# Sheet2.net
KiCad netlist of a schematic drawn in Altium Designer
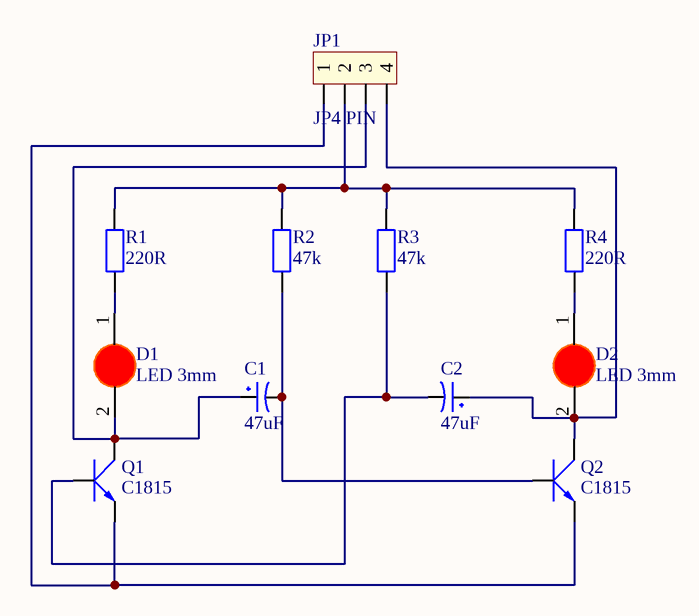
[diagram p0: Sheet2.SchDoc]

(export (version "E")
  (design (tool "Eeschema 10.0.6"))
  (components
    (comp (ref "C1")
      (value "47uF")
      (footprint "tu hoa 5mm")
      (description "Cắm")
      (libsource (lib "Capacitor") (part "Tu Hoa 47uF 16V 5x10"))
    )
    (comp (ref "C2")
      (value "47uF")
      (footprint "tu hoa 5mm")
      (description "Cắm")
      (libsource (lib "Capacitor") (part "Tu Hoa 47uF 16V 5x10"))
    )
    (comp (ref "D1")
      (value "LED 3mm")
      (footprint "LED-3MM-RED")
      (description "Cắm")
      (libsource (lib "Led") (part "LED 3mm Do"))
    )
    (comp (ref "D2")
      (value "LED 3mm")
      (footprint "LED-3MM-RED")
      (description "Cắm")
      (libsource (lib "Led") (part "LED 3mm Do"))
    )
    (comp (ref "JP1") (value "JP4 PIN") (footprint "JP4") (libsource (lib "Cty1") (part "JP4")))
    (comp (ref "Q1")
      (value "C1815")
      (footprint "TO92")
      (description "NPN transistor")
      (libsource (lib "TranFet") (part "Trans C1815 DIP"))
    )
    (comp (ref "Q2")
      (value "C1815")
      (footprint "TO92")
      (description "NPN transistor")
      (libsource (lib "TranFet") (part "Trans C1815 DIP"))
    )
    (comp (ref "R1")
      (value "220R")
      (footprint "tro vach 1/4w")
      (description "Cắm")
      (libsource (lib "Resistor") (part "Tro Vach 1/4W 5% 220R"))
    )
    (comp (ref "R2")
      (value "47k")
      (footprint "tro vach 1/4w")
      (description "Cắm")
      (libsource (lib "Resistor") (part "Tro Vach 1/4W 5% 47k"))
    )
    (comp (ref "R3")
      (value "47k")
      (footprint "tro vach 1/4w")
      (description "Cắm")
      (libsource (lib "Resistor") (part "Tro Vach 1/4W 5% 47k"))
    )
    (comp (ref "R4")
      (value "220R")
      (footprint "tro vach 1/4w")
      (description "Cắm")
      (libsource (lib "Resistor") (part "Tro Vach 1/4W 5% 220R"))
    )
  )
  (nets
    (net (code "1") (name "Net-(D1-A)") (class "Default")
      (node (ref "D1") (pin "1") (pinfunction "A_1") (pintype "passive"))
      (node (ref "R1") (pin "1") (pinfunction "1_1") (pintype "passive"))
    )
    (net (code "2") (name "Net-(D1-K)") (class "Default")
      (node (ref "C1") (pin "1") (pinfunction "1_1") (pintype "passive"))
      (node (ref "D1") (pin "2") (pinfunction "K_2") (pintype "passive"))
      (node (ref "JP1") (pin "3") (pinfunction "3_3") (pintype "passive"))
      (node (ref "Q1") (pin "2") (pinfunction "C_2") (pintype "passive"))
    )
    (net (code "3") (name "Net-(D2-A)") (class "Default")
      (node (ref "D2") (pin "1") (pinfunction "A_1") (pintype "passive"))
      (node (ref "R4") (pin "1") (pinfunction "1_1") (pintype "passive"))
    )
    (net (code "4") (name "Net-(D2-K)") (class "Default")
      (node (ref "C2") (pin "1") (pinfunction "1_1") (pintype "passive"))
      (node (ref "D2") (pin "2") (pinfunction "K_2") (pintype "passive"))
      (node (ref "JP1") (pin "4") (pinfunction "4_4") (pintype "passive"))
      (node (ref "Q2") (pin "2") (pinfunction "C_2") (pintype "passive"))
    )
    (net (code "5") (name "Net-(JP1-Pad2)") (class "Default")
      (node (ref "JP1") (pin "2") (pinfunction "2_2") (pintype "passive"))
      (node (ref "R1") (pin "2") (pinfunction "2_2") (pintype "passive"))
      (node (ref "R2") (pin "2") (pinfunction "2_2") (pintype "passive"))
      (node (ref "R3") (pin "2") (pinfunction "2_2") (pintype "passive"))
      (node (ref "R4") (pin "2") (pinfunction "2_2") (pintype "passive"))
    )
    (net (code "6") (name "Net-(Q1-B)") (class "Default")
      (node (ref "C2") (pin "2") (pinfunction "2_2") (pintype "passive"))
      (node (ref "Q1") (pin "3") (pinfunction "B_3") (pintype "passive"))
      (node (ref "R3") (pin "1") (pinfunction "1_1") (pintype "passive"))
    )
    (net (code "7") (name "Net-(Q1-E)") (class "Default")
      (node (ref "JP1") (pin "1") (pinfunction "1_1") (pintype "passive"))
      (node (ref "Q1") (pin "1") (pinfunction "E_1") (pintype "passive"))
      (node (ref "Q2") (pin "1") (pinfunction "E_1") (pintype "passive"))
    )
    (net (code "8") (name "Net-(Q2-B)") (class "Default")
      (node (ref "C1") (pin "2") (pinfunction "2_2") (pintype "passive"))
      (node (ref "Q2") (pin "3") (pinfunction "B_3") (pintype "passive"))
      (node (ref "R2") (pin "1") (pinfunction "1_1") (pintype "passive"))
    )
  )
)
